# MAIN_POWER.net
KiCad netlist of a schematic drawn in Altium Designer
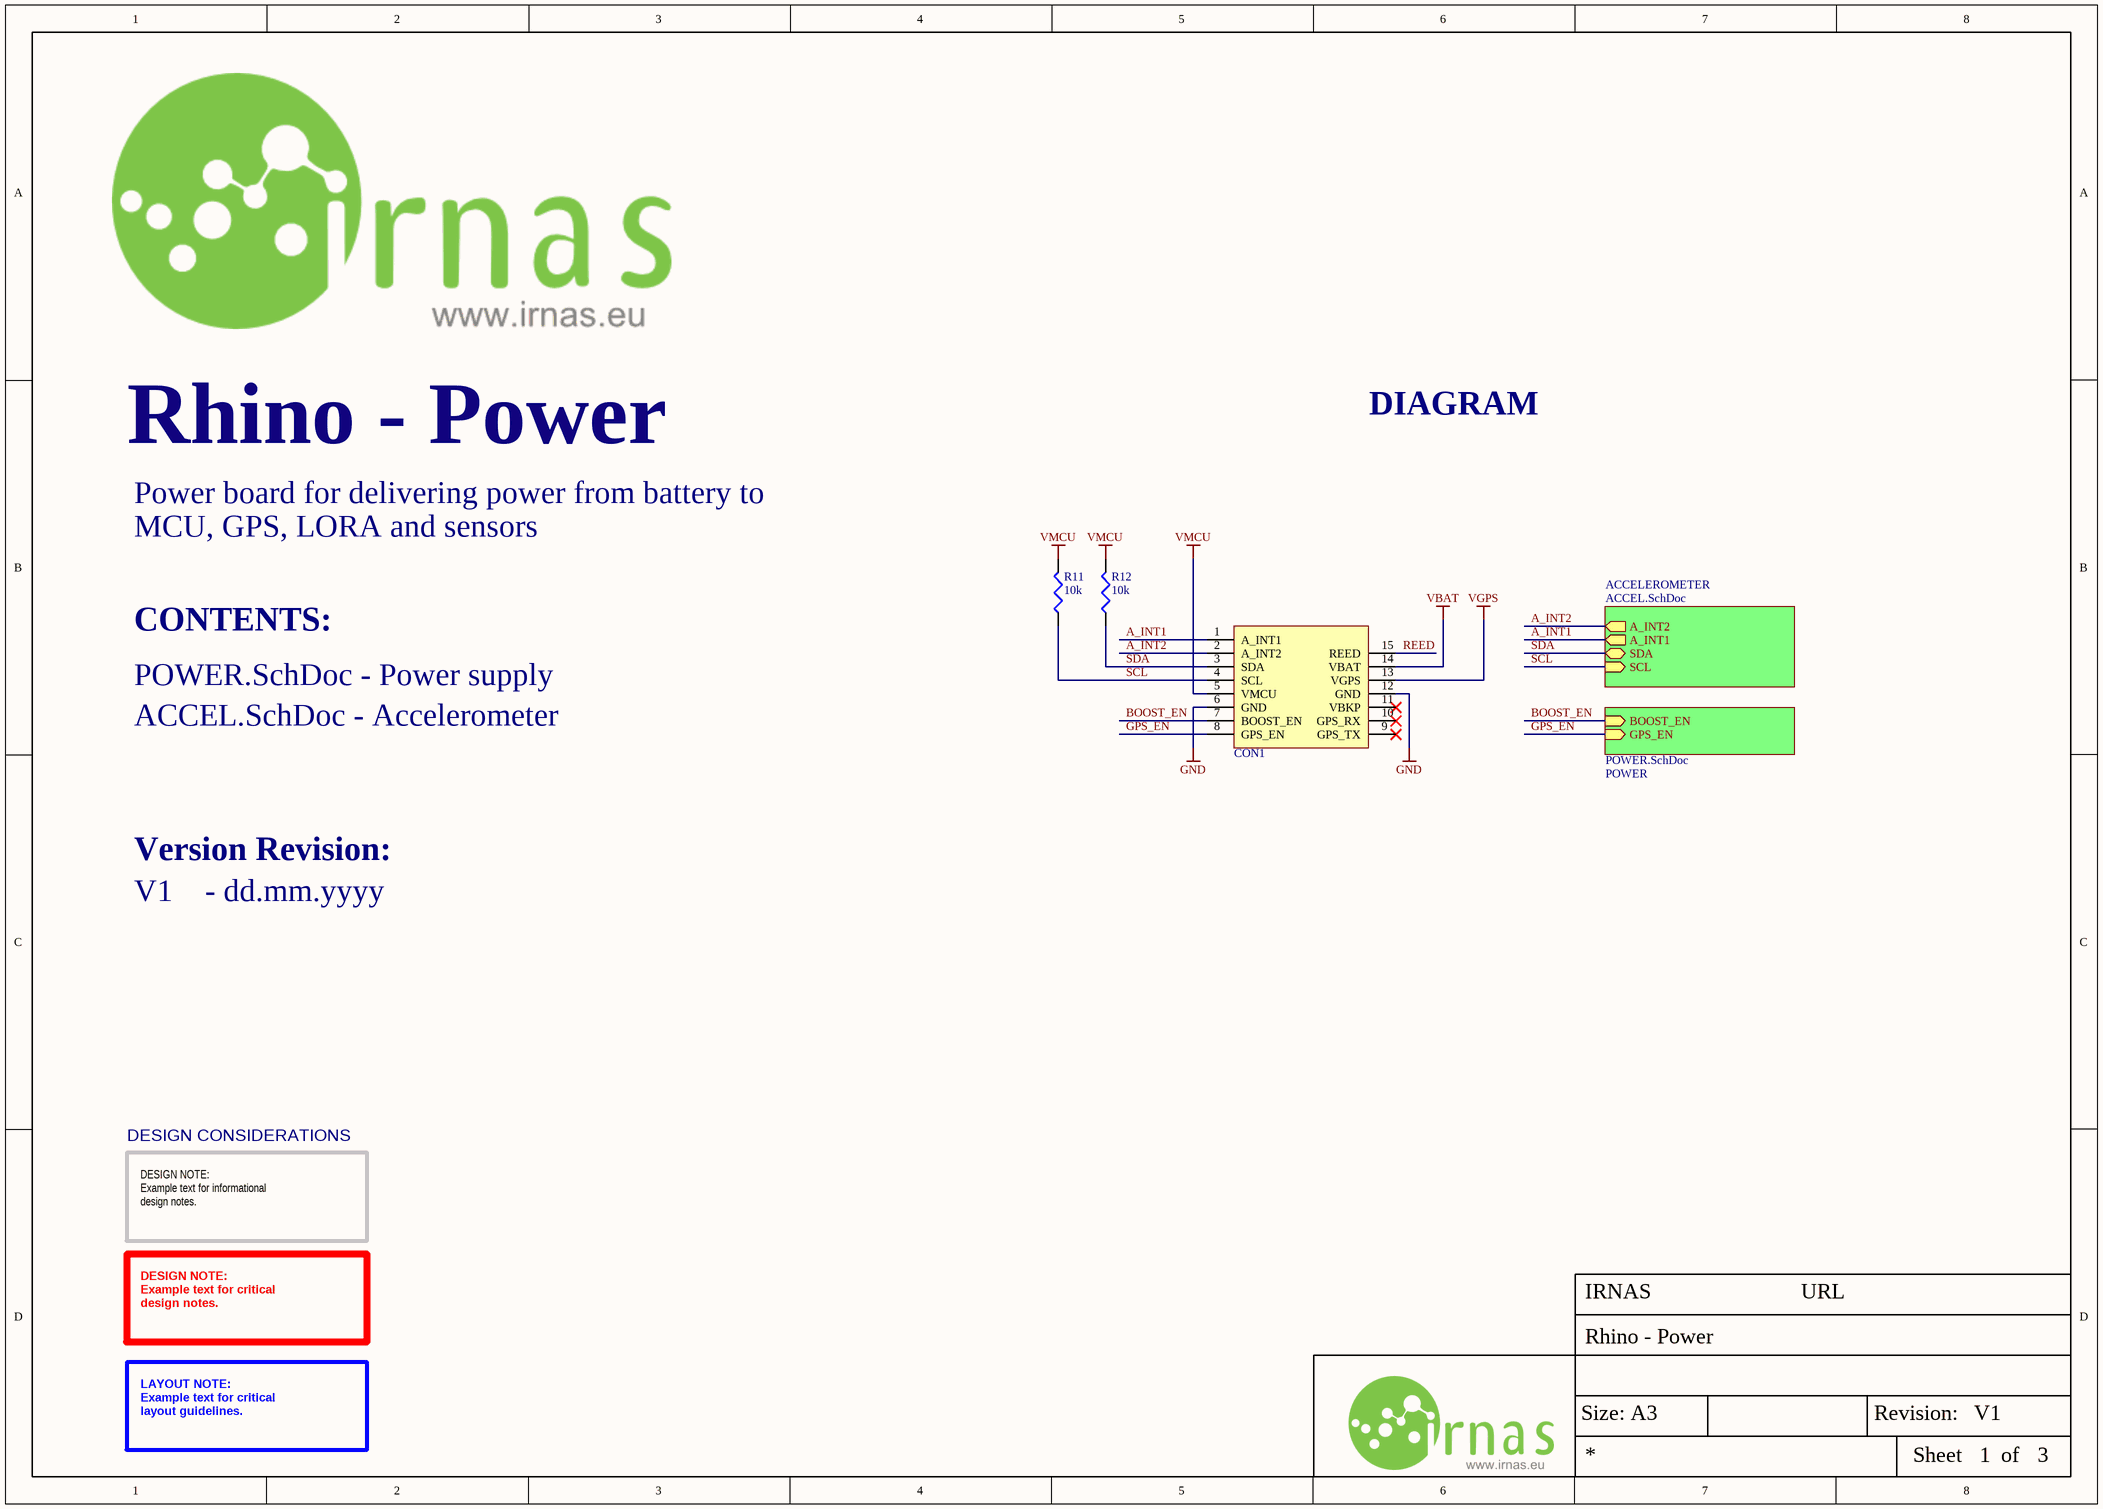
[diagram p0: MAIN_POWER.SchDoc]

(export (version "E")
  (design (tool "Eeschema 10.0.6"))
  (components
    (comp (ref "CON1")
      (value "Between PCB connection")
      (footprint "SmartParks_Rhino")
      (libsource (lib "Connectors") (part "SmartParks_Rhino"))
    )
    (comp (ref "R11")
      (value "10k")
      (footprint "RES0402")
      (fields
        (field (name "MANUFACTURER") "Multicomp")
        (field (name "MANUFACTURER PART NUMBER") "MCWR04X1002FTL")
        (field (name "TOLERANCE") "1%")
      )
      (libsource (lib "Passive") (part "R - 10k/0402"))
    )
    (comp (ref "R12")
      (value "10k")
      (footprint "RES0402")
      (fields
        (field (name "MANUFACTURER") "Multicomp")
        (field (name "MANUFACTURER PART NUMBER") "MCWR04X1002FTL")
        (field (name "TOLERANCE") "1%")
      )
      (libsource (lib "Passive") (part "R - 10k/0402"))
    )
  )
  (nets
    (net (code "1") (name "/A_INT1") (class "Default")
      (node (ref "CON1") (pin "1") (pinfunction "A_INT1_1") (pintype "passive"))
    )
    (net (code "2") (name "/A_INT2") (class "Default")
      (node (ref "CON1") (pin "2") (pinfunction "A_INT2_2") (pintype "passive"))
    )
    (net (code "3") (name "/BOOST_EN") (class "Default")
      (node (ref "CON1") (pin "7") (pinfunction "BOOST_EN_7") (pintype "passive"))
    )
    (net (code "4") (name "/GPS_EN") (class "Default")
      (node (ref "CON1") (pin "8") (pinfunction "GPS_EN_8") (pintype "passive"))
    )
    (net (code "5") (name "/REED") (class "Default")
      (node (ref "CON1") (pin "15") (pinfunction "REED_15") (pintype "passive"))
    )
    (net (code "6") (name "/SCL") (class "Default")
      (node (ref "CON1") (pin "4") (pinfunction "SCL_4") (pintype "passive"))
      (node (ref "R11") (pin "1") (pinfunction "1_1") (pintype "passive"))
    )
    (net (code "7") (name "/SDA") (class "Default")
      (node (ref "CON1") (pin "3") (pinfunction "SDA_3") (pintype "passive"))
      (node (ref "R12") (pin "1") (pinfunction "1_1") (pintype "passive"))
    )
    (net (code "8") (name "GND") (class "Default")
      (node (ref "CON1") (pin "12") (pinfunction "GND_12") (pintype "passive"))
      (node (ref "CON1") (pin "6") (pinfunction "GND_6") (pintype "passive"))
    )
    (net (code "9") (name "VBAT") (class "Default")
      (node (ref "CON1") (pin "14") (pinfunction "VBAT_14") (pintype "passive"))
    )
    (net (code "10") (name "VGPS") (class "Default")
      (node (ref "CON1") (pin "13") (pinfunction "VGPS_13") (pintype "passive"))
    )
    (net (code "11") (name "VMCU") (class "Default")
      (node (ref "CON1") (pin "5") (pinfunction "VMCU_5") (pintype "passive"))
      (node (ref "R11") (pin "2") (pinfunction "2_2") (pintype "passive"))
      (node (ref "R12") (pin "2") (pinfunction "2_2") (pintype "passive"))
    )
    (net (code "12") (name "unconnected-(CON1-GPS_RX-Pad10)") (class "Default")
      (node (ref "CON1") (pin "10") (pinfunction "GPS_RX_10") (pintype "passive+no_connect"))
    )
    (net (code "13") (name "unconnected-(CON1-GPS_TX-Pad9)") (class "Default")
      (node (ref "CON1") (pin "9") (pinfunction "GPS_TX_9") (pintype "passive+no_connect"))
    )
    (net (code "14") (name "unconnected-(CON1-VBKP-Pad11)") (class "Default")
      (node (ref "CON1") (pin "11") (pinfunction "VBKP_11") (pintype "passive+no_connect"))
    )
  )
)
